# Sheet1.net
KiCad netlist of a schematic drawn in Altium Designer
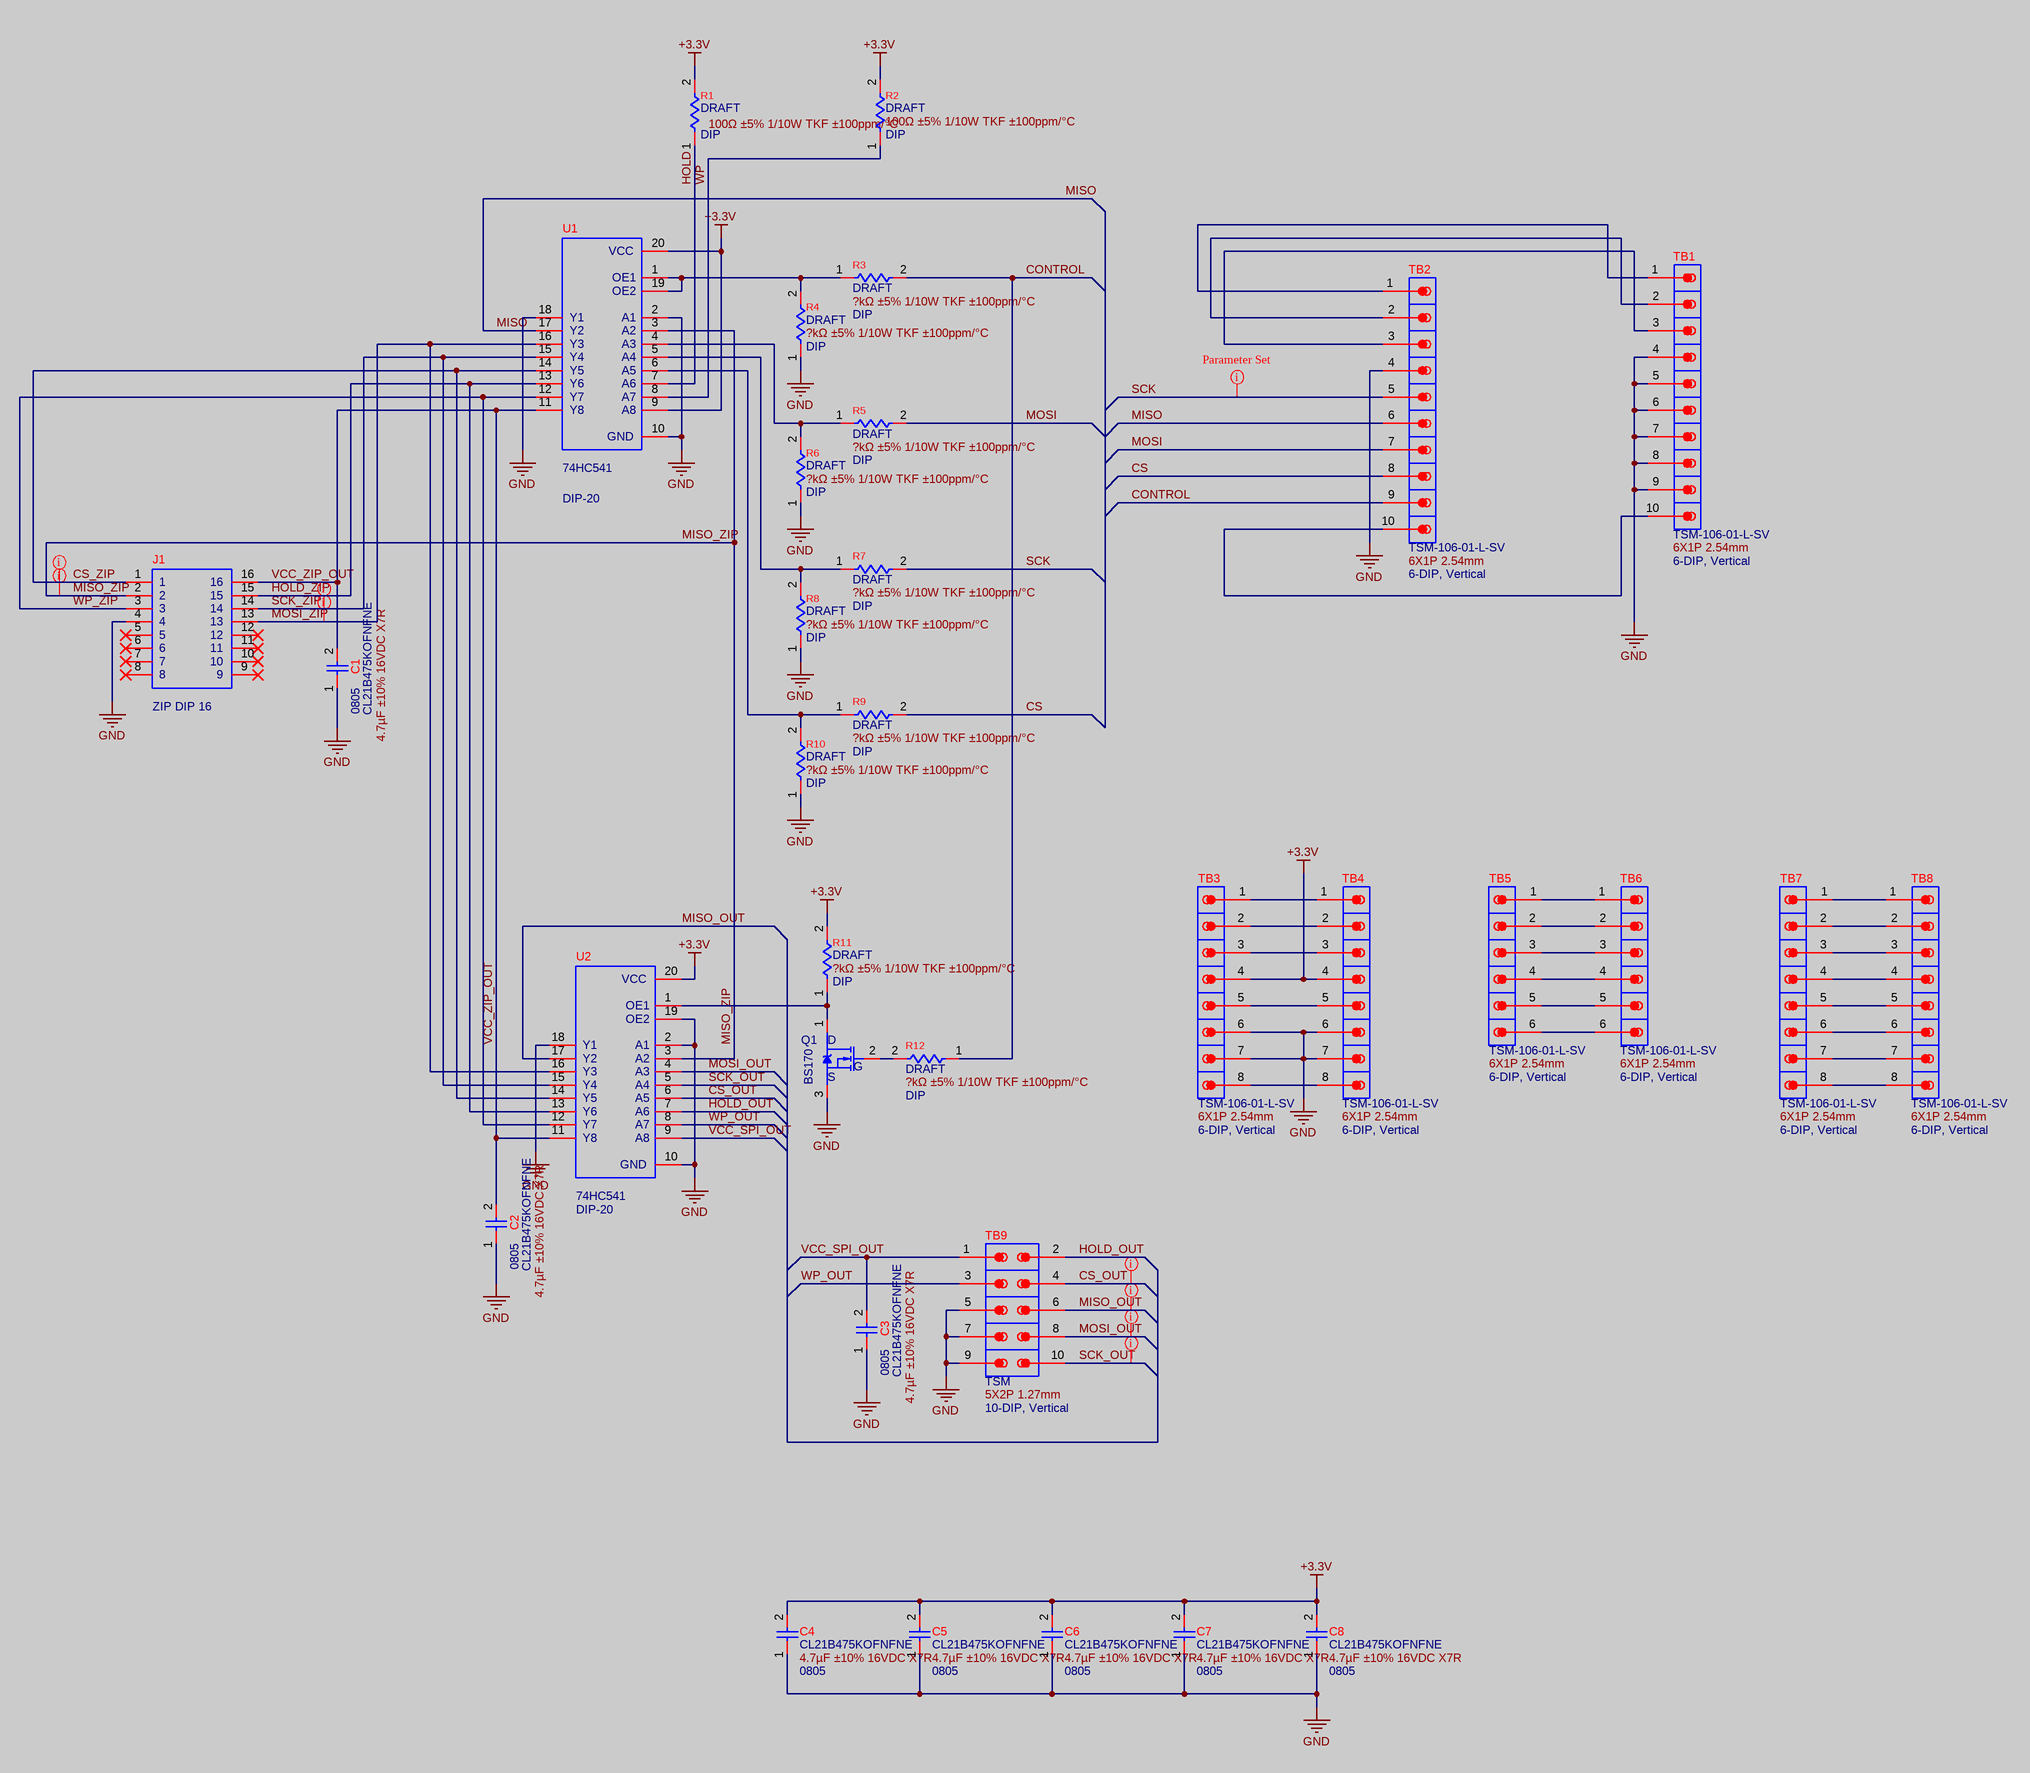
[diagram p0: Sheet1.SchDoc]

(export (version "E")
  (design (tool "Eeschema 10.0.6"))
  (components
    (comp (ref "C1")
      (value "CL21B475KOFNFNE")
      (footprint "0805_CAP_H1.4mm")
      (description "CAP CER 0805 \r\n4.7µF ±10% 25V X7R")
      (fields
        (field (name "MANUFACTURER") "SAMSUNG")
        (field (name "ALTIUM_VALUE") "4.7µF ±10% 16VDC X7R")
        (field (name "PACKAGE / CASE CODE") "0805")
      )
      (libsource (lib "Components_Library_Magenta_City") (part "CL21B475KOFNFNE"))
    )
    (comp (ref "C2")
      (value "CL21B475KOFNFNE")
      (footprint "0805_CAP_H1.4mm")
      (description "CAP CER 0805 \r\n4.7µF ±10% 25V X7R")
      (fields
        (field (name "MANUFACTURER") "SAMSUNG")
        (field (name "ALTIUM_VALUE") "4.7µF ±10% 16VDC X7R")
        (field (name "PACKAGE / CASE CODE") "0805")
      )
      (libsource (lib "Components_Library_Magenta_City") (part "CL21B475KOFNFNE"))
    )
    (comp (ref "C3")
      (value "CL21B475KOFNFNE")
      (footprint "0805_CAP_H1.4mm")
      (description "CAP CER 0805 \r\n4.7µF ±10% 25V X7R")
      (fields
        (field (name "MANUFACTURER") "SAMSUNG")
        (field (name "ALTIUM_VALUE") "4.7µF ±10% 16VDC X7R")
        (field (name "PACKAGE / CASE CODE") "0805")
      )
      (libsource (lib "Components_Library_Magenta_City") (part "CL21B475KOFNFNE"))
    )
    (comp (ref "C4")
      (value "CL21B475KOFNFNE")
      (footprint "0805_CAP_H1.4mm")
      (description "CAP CER 0805 \r\n4.7µF ±10% 25V X7R")
      (fields
        (field (name "MANUFACTURER") "SAMSUNG")
        (field (name "ALTIUM_VALUE") "4.7µF ±10% 16VDC X7R")
        (field (name "PACKAGE / CASE CODE") "0805")
      )
      (libsource (lib "Components_Library_Magenta_City") (part "CL21B475KOFNFNE"))
    )
    (comp (ref "C5")
      (value "CL21B475KOFNFNE")
      (footprint "0805_CAP_H1.4mm")
      (description "CAP CER 0805 \r\n4.7µF ±10% 25V X7R")
      (fields
        (field (name "MANUFACTURER") "SAMSUNG")
        (field (name "ALTIUM_VALUE") "4.7µF ±10% 16VDC X7R")
        (field (name "PACKAGE / CASE CODE") "0805")
      )
      (libsource (lib "Components_Library_Magenta_City") (part "CL21B475KOFNFNE"))
    )
    (comp (ref "C6")
      (value "CL21B475KOFNFNE")
      (footprint "0805_CAP_H1.4mm")
      (description "CAP CER 0805 \r\n4.7µF ±10% 25V X7R")
      (fields
        (field (name "MANUFACTURER") "SAMSUNG")
        (field (name "ALTIUM_VALUE") "4.7µF ±10% 16VDC X7R")
        (field (name "PACKAGE / CASE CODE") "0805")
      )
      (libsource (lib "Components_Library_Magenta_City") (part "CL21B475KOFNFNE"))
    )
    (comp (ref "C7")
      (value "CL21B475KOFNFNE")
      (footprint "0805_CAP_H1.4mm")
      (description "CAP CER 0805 \r\n4.7µF ±10% 25V X7R")
      (fields
        (field (name "MANUFACTURER") "SAMSUNG")
        (field (name "ALTIUM_VALUE") "4.7µF ±10% 16VDC X7R")
        (field (name "PACKAGE / CASE CODE") "0805")
      )
      (libsource (lib "Components_Library_Magenta_City") (part "CL21B475KOFNFNE"))
    )
    (comp (ref "C8")
      (value "CL21B475KOFNFNE")
      (footprint "0805_CAP_H1.4mm")
      (description "CAP CER 0805 \r\n4.7µF ±10% 25V X7R")
      (fields
        (field (name "MANUFACTURER") "SAMSUNG")
        (field (name "ALTIUM_VALUE") "4.7µF ±10% 16VDC X7R")
        (field (name "PACKAGE / CASE CODE") "0805")
      )
      (libsource (lib "Components_Library_Magenta_City") (part "CL21B475KOFNFNE"))
    )
    (comp (ref "J1")
      (value "ZIP DIP 16")
      (footprint "DIP-16")
      (description "3M™ Textool™.100” (2.54 mm) DIP Sockets\r\nZIP DIP")
      (fields (field (name "MANUFACTURER") "TI"))
      (libsource (lib "Magenta_City_lib") (part "ZIP DIP 16"))
    )
    (comp (ref "Q1")
      (value "BS170")
      (footprint "TO-226-AA")
      (description "MOSFET N-Channel")
      (libsource (lib "Components_Library_Magenta_City") (part "BS170"))
    )
    (comp (ref "R1")
      (value "DRAFT")
      (footprint "RES-DIP")
      (description "RES DRAFT DIP")
      (fields
        (field (name "ALTIUM_VALUE") "100Ω ±5% 1/10W TKF ±100ppm/°C")
        (field (name "PACKAGE / CASE CODE") "DIP")
      )
      (libsource (lib "Components_Library_Magenta_City") (part "Res DIP"))
    )
    (comp (ref "R2")
      (value "DRAFT")
      (footprint "RES-DIP")
      (description "RES DRAFT DIP")
      (fields
        (field (name "ALTIUM_VALUE") "100Ω ±5% 1/10W TKF ±100ppm/°C")
        (field (name "PACKAGE / CASE CODE") "DIP")
      )
      (libsource (lib "Components_Library_Magenta_City") (part "Res DIP"))
    )
    (comp (ref "R3")
      (value "DRAFT")
      (footprint "RES-DIP")
      (description "RES DRAFT DIP")
      (fields
        (field (name "ALTIUM_VALUE") "?kΩ ±5% 1/10W TKF ±100ppm/°C")
        (field (name "PACKAGE / CASE CODE") "DIP")
      )
      (libsource (lib "Components_Library_Magenta_City") (part "Res DIP"))
    )
    (comp (ref "R4")
      (value "DRAFT")
      (footprint "RES-DIP")
      (description "RES DRAFT DIP")
      (fields
        (field (name "ALTIUM_VALUE") "?kΩ ±5% 1/10W TKF ±100ppm/°C")
        (field (name "PACKAGE / CASE CODE") "DIP")
      )
      (libsource (lib "Components_Library_Magenta_City") (part "Res DIP"))
    )
    (comp (ref "R5")
      (value "DRAFT")
      (footprint "RES-DIP")
      (description "RES DRAFT DIP")
      (fields
        (field (name "ALTIUM_VALUE") "?kΩ ±5% 1/10W TKF ±100ppm/°C")
        (field (name "PACKAGE / CASE CODE") "DIP")
      )
      (libsource (lib "Components_Library_Magenta_City") (part "Res DIP"))
    )
    (comp (ref "R6")
      (value "DRAFT")
      (footprint "RES-DIP")
      (description "RES DRAFT DIP")
      (fields
        (field (name "ALTIUM_VALUE") "?kΩ ±5% 1/10W TKF ±100ppm/°C")
        (field (name "PACKAGE / CASE CODE") "DIP")
      )
      (libsource (lib "Components_Library_Magenta_City") (part "Res DIP"))
    )
    (comp (ref "R7")
      (value "DRAFT")
      (footprint "RES-DIP")
      (description "RES DRAFT DIP")
      (fields
        (field (name "ALTIUM_VALUE") "?kΩ ±5% 1/10W TKF ±100ppm/°C")
        (field (name "PACKAGE / CASE CODE") "DIP")
      )
      (libsource (lib "Components_Library_Magenta_City") (part "Res DIP"))
    )
    (comp (ref "R8")
      (value "DRAFT")
      (footprint "RES-DIP")
      (description "RES DRAFT DIP")
      (fields
        (field (name "ALTIUM_VALUE") "?kΩ ±5% 1/10W TKF ±100ppm/°C")
        (field (name "PACKAGE / CASE CODE") "DIP")
      )
      (libsource (lib "Components_Library_Magenta_City") (part "Res DIP"))
    )
    (comp (ref "R9")
      (value "DRAFT")
      (footprint "RES-DIP")
      (description "RES DRAFT DIP")
      (fields
        (field (name "ALTIUM_VALUE") "?kΩ ±5% 1/10W TKF ±100ppm/°C")
        (field (name "PACKAGE / CASE CODE") "DIP")
      )
      (libsource (lib "Components_Library_Magenta_City") (part "Res DIP"))
    )
    (comp (ref "R10")
      (value "DRAFT")
      (footprint "RES-DIP")
      (description "RES DRAFT DIP")
      (fields
        (field (name "ALTIUM_VALUE") "?kΩ ±5% 1/10W TKF ±100ppm/°C")
        (field (name "PACKAGE / CASE CODE") "DIP")
      )
      (libsource (lib "Components_Library_Magenta_City") (part "Res DIP"))
    )
    (comp (ref "R11")
      (value "DRAFT")
      (footprint "RES-DIP")
      (description "RES DRAFT DIP")
      (fields
        (field (name "ALTIUM_VALUE") "?kΩ ±5% 1/10W TKF ±100ppm/°C")
        (field (name "PACKAGE / CASE CODE") "DIP")
      )
      (libsource (lib "Components_Library_Magenta_City") (part "Res DIP"))
    )
    (comp (ref "R12")
      (value "DRAFT")
      (footprint "RES-DIP")
      (description "RES DRAFT DIP")
      (fields
        (field (name "ALTIUM_VALUE") "?kΩ ±5% 1/10W TKF ±100ppm/°C")
        (field (name "PACKAGE / CASE CODE") "DIP")
      )
      (libsource (lib "Components_Library_Magenta_City") (part "Res DIP"))
    )
    (comp (ref "TB1")
      (value "TSM-106-01-L-SV")
      (footprint "SW10")
      (description "TERMINAL STRIP \r\n2.54mm 6X1P \r\nSMD Vertical")
      (fields
        (field (name "MANUFACTURER") "Samtec")
        (field (name "ALTIUM_VALUE") "6X1P 2.54mm")
        (field (name "PACKAGE / CASE CODE") "6-DIP, Vertical")
      )
      (libsource (lib "Components_Library_Magenta_City") (part "SW-10"))
    )
    (comp (ref "TB2")
      (value "TSM-106-01-L-SV")
      (footprint "SW10")
      (description "TERMINAL STRIP \r\n2.54mm 6X1P \r\nSMD Vertical")
      (fields
        (field (name "MANUFACTURER") "Samtec")
        (field (name "ALTIUM_VALUE") "6X1P 2.54mm")
        (field (name "PACKAGE / CASE CODE") "6-DIP, Vertical")
      )
      (libsource (lib "Components_Library_Magenta_City") (part "SW-10"))
    )
    (comp (ref "TB3")
      (value "TSM-106-01-L-SV")
      (footprint "SW8")
      (description "TERMINAL STRIP \r\n2.54mm 6X1P \r\nSMD Vertical")
      (fields
        (field (name "MANUFACTURER") "Samtec")
        (field (name "ALTIUM_VALUE") "6X1P 2.54mm")
        (field (name "PACKAGE / CASE CODE") "6-DIP, Vertical")
      )
      (libsource (lib "") (part "SW-8_1"))
    )
    (comp (ref "TB4")
      (value "TSM-106-01-L-SV")
      (footprint "SW8")
      (description "TERMINAL STRIP \r\n2.54mm 6X1P \r\nSMD Vertical")
      (fields
        (field (name "MANUFACTURER") "Samtec")
        (field (name "ALTIUM_VALUE") "6X1P 2.54mm")
        (field (name "PACKAGE / CASE CODE") "6-DIP, Vertical")
      )
      (libsource (lib "Components_Library_Magenta_City") (part "SW-8"))
    )
    (comp (ref "TB5")
      (value "TSM-106-01-L-SV")
      (footprint "SW6")
      (description "TERMINAL STRIP \r\n2.54mm 6X1P \r\nSMD Vertical")
      (fields
        (field (name "MANUFACTURER") "Samtec")
        (field (name "ALTIUM_VALUE") "6X1P 2.54mm")
        (field (name "PACKAGE / CASE CODE") "6-DIP, Vertical")
      )
      (libsource (lib "") (part "SW-6_1"))
    )
    (comp (ref "TB6")
      (value "TSM-106-01-L-SV")
      (footprint "SW6")
      (description "TERMINAL STRIP \r\n2.54mm 6X1P \r\nSMD Vertical")
      (fields
        (field (name "MANUFACTURER") "Samtec")
        (field (name "ALTIUM_VALUE") "6X1P 2.54mm")
        (field (name "PACKAGE / CASE CODE") "6-DIP, Vertical")
      )
      (libsource (lib "Components_Library_Magenta_City") (part "SW-6"))
    )
    (comp (ref "TB7")
      (value "TSM-106-01-L-SV")
      (footprint "SW8")
      (description "TERMINAL STRIP \r\n2.54mm 6X1P \r\nSMD Vertical")
      (fields
        (field (name "MANUFACTURER") "Samtec")
        (field (name "ALTIUM_VALUE") "6X1P 2.54mm")
        (field (name "PACKAGE / CASE CODE") "6-DIP, Vertical")
      )
      (libsource (lib "") (part "SW-8_1"))
    )
    (comp (ref "TB8")
      (value "TSM-106-01-L-SV")
      (footprint "SW8")
      (description "TERMINAL STRIP \r\n2.54mm 6X1P \r\nSMD Vertical")
      (fields
        (field (name "MANUFACTURER") "Samtec")
        (field (name "ALTIUM_VALUE") "6X1P 2.54mm")
        (field (name "PACKAGE / CASE CODE") "6-DIP, Vertical")
      )
      (libsource (lib "Components_Library_Magenta_City") (part "SW-8"))
    )
    (comp (ref "TB9")
      (value "TSM")
      (footprint "SW10x2_1.27")
      (description "TERMINAL STRIP \r\n1.27mm 5X2P \r\nDIP Vertical")
      (fields
        (field (name "MANUFACTURER") "Samtec")
        (field (name "ALTIUM_VALUE") "5X2P 1.27mm")
        (field (name "PACKAGE / CASE CODE") "10-DIP, Vertical")
      )
      (libsource (lib "Components_Library_Magenta_City") (part "TSM-1"))
    )
    (comp (ref "U1")
      (value "74HC541")
      (footprint "CDIP-20")
      (description "DIP-20")
      (fields (field (name "MANUFACTURER") "TI") (field (name "PACKAGE / CASE CODE") "DIP-20"))
      (libsource (lib "Components_Library_Magenta_City") (part "74HC541"))
    )
    (comp (ref "U2")
      (value "74HC541")
      (footprint "CDIP-20")
      (description "DIP-20")
      (fields (field (name "MANUFACTURER") "TI") (field (name "PACKAGE / CASE CODE") "DIP-20"))
      (libsource (lib "Components_Library_Magenta_City") (part "74HC541"))
    )
  )
  (nets
    (net (code "1") (name "+3.3V") (class "Default")
      (node (ref "C4") (pin "2") (pinfunction "2_2") (pintype "passive"))
      (node (ref "C5") (pin "2") (pinfunction "2_2") (pintype "passive"))
      (node (ref "C6") (pin "2") (pinfunction "2_2") (pintype "passive"))
      (node (ref "C7") (pin "2") (pinfunction "2_2") (pintype "passive"))
      (node (ref "C8") (pin "2") (pinfunction "2_2") (pintype "passive"))
      (node (ref "R1") (pin "2") (pinfunction "2_2") (pintype "passive"))
      (node (ref "R11") (pin "2") (pinfunction "2_2") (pintype "passive"))
      (node (ref "R2") (pin "2") (pinfunction "2_2") (pintype "passive"))
      (node (ref "TB3") (pin "4") (pinfunction "4_4") (pintype "passive"))
      (node (ref "TB4") (pin "4") (pinfunction "4_4") (pintype "passive"))
      (node (ref "U1") (pin "20") (pinfunction "VCC_20") (pintype "power_in"))
      (node (ref "U1") (pin "9") (pinfunction "A8_9") (pintype "passive"))
      (node (ref "U2") (pin "20") (pinfunction "VCC_20") (pintype "power_in"))
    )
    (net (code "2") (name "/CONTROL") (class "Default")
      (node (ref "R12") (pin "1") (pinfunction "1_1") (pintype "passive"))
      (node (ref "R3") (pin "2") (pinfunction "2_2") (pintype "passive"))
      (node (ref "TB2") (pin "9") (pinfunction "9_9") (pintype "passive"))
    )
    (net (code "3") (name "/CS") (class "Default")
      (node (ref "R9") (pin "2") (pinfunction "2_2") (pintype "passive"))
      (node (ref "TB2") (pin "8") (pinfunction "8_8") (pintype "passive"))
    )
    (net (code "4") (name "/CS_OUT") (class "Default")
      (node (ref "TB9") (pin "4") (pinfunction "4_4") (pintype "passive"))
      (node (ref "U2") (pin "6") (pinfunction "A5_6") (pintype "passive"))
    )
    (net (code "5") (name "/CS_ZIP") (class "Default")
      (node (ref "J1") (pin "1") (pinfunction "1_1") (pintype "passive"))
      (node (ref "U1") (pin "14") (pinfunction "Y5_14") (pintype "passive"))
      (node (ref "U2") (pin "14") (pinfunction "Y5_14") (pintype "passive"))
    )
    (net (code "6") (name "/HOLD") (class "Default")
      (node (ref "R1") (pin "1") (pinfunction "1_1") (pintype "passive"))
      (node (ref "U1") (pin "7") (pinfunction "A6_7") (pintype "passive"))
    )
    (net (code "7") (name "/HOLD_OUT") (class "Default")
      (node (ref "TB9") (pin "2") (pinfunction "2_2") (pintype "passive"))
      (node (ref "U2") (pin "7") (pinfunction "A6_7") (pintype "passive"))
    )
    (net (code "8") (name "/HOLD_ZIP") (class "Default")
      (node (ref "J1") (pin "15") (pinfunction "15_15") (pintype "passive"))
      (node (ref "U1") (pin "13") (pinfunction "Y6_13") (pintype "passive"))
      (node (ref "U2") (pin "13") (pinfunction "Y6_13") (pintype "passive"))
    )
    (net (code "9") (name "/MISO") (class "Default")
      (node (ref "TB2") (pin "6") (pinfunction "6_6") (pintype "passive"))
      (node (ref "U1") (pin "17") (pinfunction "Y2_17") (pintype "passive"))
    )
    (net (code "10") (name "/MISO_OUT") (class "Default")
      (node (ref "TB9") (pin "6") (pinfunction "6_6") (pintype "passive"))
      (node (ref "U2") (pin "17") (pinfunction "Y2_17") (pintype "passive"))
    )
    (net (code "11") (name "/MISO_ZIP") (class "Default")
      (node (ref "J1") (pin "2") (pinfunction "2_2") (pintype "passive"))
      (node (ref "U1") (pin "3") (pinfunction "A2_3") (pintype "passive"))
      (node (ref "U2") (pin "3") (pinfunction "A2_3") (pintype "passive"))
    )
    (net (code "12") (name "/MOSI") (class "Default")
      (node (ref "R5") (pin "2") (pinfunction "2_2") (pintype "passive"))
      (node (ref "TB2") (pin "7") (pinfunction "7_7") (pintype "passive"))
    )
    (net (code "13") (name "/MOSI_OUT") (class "Default")
      (node (ref "TB9") (pin "8") (pinfunction "8_8") (pintype "passive"))
      (node (ref "U2") (pin "4") (pinfunction "A3_4") (pintype "passive"))
    )
    (net (code "14") (name "/MOSI_ZIP") (class "Default")
      (node (ref "J1") (pin "13") (pinfunction "13_13") (pintype "passive"))
      (node (ref "U1") (pin "16") (pinfunction "Y3_16") (pintype "passive"))
      (node (ref "U2") (pin "16") (pinfunction "Y3_16") (pintype "passive"))
    )
    (net (code "15") (name "/SCK") (class "Default")
      (node (ref "R7") (pin "2") (pinfunction "2_2") (pintype "passive"))
      (node (ref "TB2") (pin "5") (pinfunction "5_5") (pintype "passive"))
    )
    (net (code "16") (name "/SCK_OUT") (class "Default")
      (node (ref "TB9") (pin "10") (pinfunction "10_10") (pintype "passive"))
      (node (ref "U2") (pin "5") (pinfunction "A4_5") (pintype "passive"))
    )
    (net (code "17") (name "/SCK_ZIP") (class "Default")
      (node (ref "J1") (pin "14") (pinfunction "14_14") (pintype "passive"))
      (node (ref "U1") (pin "15") (pinfunction "Y4_15") (pintype "passive"))
      (node (ref "U2") (pin "15") (pinfunction "Y4_15") (pintype "passive"))
    )
    (net (code "18") (name "/VCC_SPI_OUT") (class "Default")
      (node (ref "C3") (pin "2") (pinfunction "2_2") (pintype "passive"))
      (node (ref "TB9") (pin "1") (pinfunction "1_1") (pintype "passive"))
      (node (ref "U2") (pin "9") (pinfunction "A8_9") (pintype "passive"))
    )
    (net (code "19") (name "/VCC_ZIP_OUT") (class "Default")
      (node (ref "C1") (pin "2") (pinfunction "2_2") (pintype "passive"))
      (node (ref "C2") (pin "2") (pinfunction "2_2") (pintype "passive"))
      (node (ref "J1") (pin "16") (pinfunction "16_16") (pintype "passive"))
      (node (ref "U1") (pin "11") (pinfunction "Y8_11") (pintype "passive"))
      (node (ref "U2") (pin "11") (pinfunction "Y8_11") (pintype "passive"))
    )
    (net (code "20") (name "/WP") (class "Default")
      (node (ref "R2") (pin "1") (pinfunction "1_1") (pintype "passive"))
      (node (ref "U1") (pin "8") (pinfunction "A7_8") (pintype "passive"))
    )
    (net (code "21") (name "/WP_OUT") (class "Default")
      (node (ref "TB9") (pin "3") (pinfunction "3_3") (pintype "passive"))
      (node (ref "U2") (pin "8") (pinfunction "A7_8") (pintype "passive"))
    )
    (net (code "22") (name "/WP_ZIP") (class "Default")
      (node (ref "J1") (pin "3") (pinfunction "3_3") (pintype "passive"))
      (node (ref "U1") (pin "12") (pinfunction "Y7_12") (pintype "passive"))
      (node (ref "U2") (pin "12") (pinfunction "Y7_12") (pintype "passive"))
    )
    (net (code "23") (name "GND") (class "Default")
      (node (ref "C1") (pin "1") (pinfunction "1_1") (pintype "passive"))
      (node (ref "C2") (pin "1") (pinfunction "1_1") (pintype "passive"))
      (node (ref "C3") (pin "1") (pinfunction "1_1") (pintype "passive"))
      (node (ref "C4") (pin "1") (pinfunction "1_1") (pintype "passive"))
      (node (ref "C5") (pin "1") (pinfunction "1_1") (pintype "passive"))
      (node (ref "C6") (pin "1") (pinfunction "1_1") (pintype "passive"))
      (node (ref "C7") (pin "1") (pinfunction "1_1") (pintype "passive"))
      (node (ref "C8") (pin "1") (pinfunction "1_1") (pintype "passive"))
      (node (ref "J1") (pin "4") (pinfunction "4_4") (pintype "passive"))
      (node (ref "Q1") (pin "3") (pinfunction "S_3") (pintype "passive"))
      (node (ref "R10") (pin "1") (pinfunction "1_1") (pintype "passive"))
      (node (ref "R4") (pin "1") (pinfunction "1_1") (pintype "passive"))
      (node (ref "R6") (pin "1") (pinfunction "1_1") (pintype "passive"))
      (node (ref "R8") (pin "1") (pinfunction "1_1") (pintype "passive"))
      (node (ref "TB1") (pin "4") (pinfunction "4_4") (pintype "passive"))
      (node (ref "TB1") (pin "5") (pinfunction "5_5") (pintype "passive"))
      (node (ref "TB1") (pin "6") (pinfunction "6_6") (pintype "passive"))
      (node (ref "TB1") (pin "7") (pinfunction "7_7") (pintype "passive"))
      (node (ref "TB1") (pin "8") (pinfunction "8_8") (pintype "passive"))
      (node (ref "TB1") (pin "9") (pinfunction "9_9") (pintype "passive"))
      (node (ref "TB2") (pin "4") (pinfunction "4_4") (pintype "passive"))
      (node (ref "TB3") (pin "6") (pinfunction "6_6") (pintype "passive"))
      (node (ref "TB3") (pin "7") (pinfunction "7_7") (pintype "passive"))
      (node (ref "TB4") (pin "6") (pinfunction "6_6") (pintype "passive"))
      (node (ref "TB4") (pin "7") (pinfunction "7_7") (pintype "passive"))
      (node (ref "TB9") (pin "5") (pinfunction "5_5") (pintype "passive"))
      (node (ref "TB9") (pin "7") (pinfunction "7_7") (pintype "passive"))
      (node (ref "TB9") (pin "9") (pinfunction "9_9") (pintype "passive"))
      (node (ref "U1") (pin "10") (pinfunction "GND_10") (pintype "power_in"))
      (node (ref "U1") (pin "18") (pinfunction "Y1_18") (pintype "passive"))
      (node (ref "U1") (pin "2") (pinfunction "A1_2") (pintype "passive"))
      (node (ref "U2") (pin "10") (pinfunction "GND_10") (pintype "power_in"))
      (node (ref "U2") (pin "18") (pinfunction "Y1_18") (pintype "passive"))
      (node (ref "U2") (pin "19") (pinfunction "OE2_19") (pintype "passive"))
      (node (ref "U2") (pin "2") (pinfunction "A1_2") (pintype "passive"))
    )
    (net (code "24") (name "Net-(Q1-D)") (class "Default")
      (node (ref "Q1") (pin "1") (pinfunction "D_1") (pintype "passive"))
      (node (ref "R11") (pin "1") (pinfunction "1_1") (pintype "passive"))
      (node (ref "U2") (pin "1") (pinfunction "OE1_1") (pintype "passive"))
    )
    (net (code "25") (name "Net-(Q1-G)") (class "Default")
      (node (ref "Q1") (pin "2") (pinfunction "G_2") (pintype "passive"))
      (node (ref "R12") (pin "2") (pinfunction "2_2") (pintype "passive"))
    )
    (net (code "26") (name "Net-(TB1-Pad1)") (class "Default")
      (node (ref "TB1") (pin "1") (pinfunction "1_1") (pintype "passive"))
      (node (ref "TB2") (pin "1") (pinfunction "1_1") (pintype "passive"))
    )
    (net (code "27") (name "Net-(TB1-Pad2)") (class "Default")
      (node (ref "TB1") (pin "2") (pinfunction "2_2") (pintype "passive"))
      (node (ref "TB2") (pin "2") (pinfunction "2_2") (pintype "passive"))
    )
    (net (code "28") (name "Net-(TB1-Pad3)") (class "Default")
      (node (ref "TB1") (pin "3") (pinfunction "3_3") (pintype "passive"))
      (node (ref "TB2") (pin "3") (pinfunction "3_3") (pintype "passive"))
    )
    (net (code "29") (name "Net-(TB1-Pad10)") (class "Default")
      (node (ref "TB1") (pin "10") (pinfunction "10_10") (pintype "passive"))
      (node (ref "TB2") (pin "10") (pinfunction "10_10") (pintype "passive"))
    )
    (net (code "30") (name "Net-(TB3-Pad1)") (class "Default")
      (node (ref "TB3") (pin "1") (pinfunction "1_1") (pintype "passive"))
      (node (ref "TB4") (pin "1") (pinfunction "1_1") (pintype "passive"))
    )
    (net (code "31") (name "Net-(TB3-Pad2)") (class "Default")
      (node (ref "TB3") (pin "2") (pinfunction "2_2") (pintype "passive"))
      (node (ref "TB4") (pin "2") (pinfunction "2_2") (pintype "passive"))
    )
    (net (code "32") (name "Net-(TB3-Pad3)") (class "Default")
      (node (ref "TB3") (pin "3") (pinfunction "3_3") (pintype "passive"))
      (node (ref "TB4") (pin "3") (pinfunction "3_3") (pintype "passive"))
    )
    (net (code "33") (name "Net-(TB3-Pad5)") (class "Default")
      (node (ref "TB3") (pin "5") (pinfunction "5_5") (pintype "passive"))
      (node (ref "TB4") (pin "5") (pinfunction "5_5") (pintype "passive"))
    )
    (net (code "34") (name "Net-(TB3-Pad8)") (class "Default")
      (node (ref "TB3") (pin "8") (pinfunction "8_8") (pintype "passive"))
      (node (ref "TB4") (pin "8") (pinfunction "8_8") (pintype "passive"))
    )
    (net (code "35") (name "Net-(TB5-Pad1)") (class "Default")
      (node (ref "TB5") (pin "1") (pinfunction "1_1") (pintype "passive"))
      (node (ref "TB6") (pin "1") (pinfunction "1_1") (pintype "passive"))
    )
    (net (code "36") (name "Net-(TB5-Pad2)") (class "Default")
      (node (ref "TB5") (pin "2") (pinfunction "2_2") (pintype "passive"))
      (node (ref "TB6") (pin "2") (pinfunction "2_2") (pintype "passive"))
    )
    (net (code "37") (name "Net-(TB5-Pad3)") (class "Default")
      (node (ref "TB5") (pin "3") (pinfunction "3_3") (pintype "passive"))
      (node (ref "TB6") (pin "3") (pinfunction "3_3") (pintype "passive"))
    )
    (net (code "38") (name "Net-(TB5-Pad4)") (class "Default")
      (node (ref "TB5") (pin "4") (pinfunction "4_4") (pintype "passive"))
      (node (ref "TB6") (pin "4") (pinfunction "4_4") (pintype "passive"))
    )
    (net (code "39") (name "Net-(TB5-Pad5)") (class "Default")
      (node (ref "TB5") (pin "5") (pinfunction "5_5") (pintype "passive"))
      (node (ref "TB6") (pin "5") (pinfunction "5_5") (pintype "passive"))
    )
    (net (code "40") (name "Net-(TB5-Pad6)") (class "Default")
      (node (ref "TB5") (pin "6") (pinfunction "6_6") (pintype "passive"))
      (node (ref "TB6") (pin "6") (pinfunction "6_6") (pintype "passive"))
    )
    (net (code "41") (name "Net-(TB7-Pad1)") (class "Default")
      (node (ref "TB7") (pin "1") (pinfunction "1_1") (pintype "passive"))
      (node (ref "TB8") (pin "1") (pinfunction "1_1") (pintype "passive"))
    )
    (net (code "42") (name "Net-(TB7-Pad2)") (class "Default")
      (node (ref "TB7") (pin "2") (pinfunction "2_2") (pintype "passive"))
      (node (ref "TB8") (pin "2") (pinfunction "2_2") (pintype "passive"))
    )
    (net (code "43") (name "Net-(TB7-Pad3)") (class "Default")
      (node (ref "TB7") (pin "3") (pinfunction "3_3") (pintype "passive"))
      (node (ref "TB8") (pin "3") (pinfunction "3_3") (pintype "passive"))
    )
    (net (code "44") (name "Net-(TB7-Pad4)") (class "Default")
      (node (ref "TB7") (pin "4") (pinfunction "4_4") (pintype "passive"))
      (node (ref "TB8") (pin "4") (pinfunction "4_4") (pintype "passive"))
    )
    (net (code "45") (name "Net-(TB7-Pad5)") (class "Default")
      (node (ref "TB7") (pin "5") (pinfunction "5_5") (pintype "passive"))
      (node (ref "TB8") (pin "5") (pinfunction "5_5") (pintype "passive"))
    )
    (net (code "46") (name "Net-(TB7-Pad6)") (class "Default")
      (node (ref "TB7") (pin "6") (pinfunction "6_6") (pintype "passive"))
      (node (ref "TB8") (pin "6") (pinfunction "6_6") (pintype "passive"))
    )
    (net (code "47") (name "Net-(TB7-Pad7)") (class "Default")
      (node (ref "TB7") (pin "7") (pinfunction "7_7") (pintype "passive"))
      (node (ref "TB8") (pin "7") (pinfunction "7_7") (pintype "passive"))
    )
    (net (code "48") (name "Net-(TB7-Pad8)") (class "Default")
      (node (ref "TB7") (pin "8") (pinfunction "8_8") (pintype "passive"))
      (node (ref "TB8") (pin "8") (pinfunction "8_8") (pintype "passive"))
    )
    (net (code "49") (name "Net-(U1-A3)") (class "Default")
      (node (ref "R5") (pin "1") (pinfunction "1_1") (pintype "passive"))
      (node (ref "R6") (pin "2") (pinfunction "2_2") (pintype "passive"))
      (node (ref "U1") (pin "4") (pinfunction "A3_4") (pintype "passive"))
    )
    (net (code "50") (name "Net-(U1-A4)") (class "Default")
      (node (ref "R7") (pin "1") (pinfunction "1_1") (pintype "passive"))
      (node (ref "R8") (pin "2") (pinfunction "2_2") (pintype "passive"))
      (node (ref "U1") (pin "5") (pinfunction "A4_5") (pintype "passive"))
    )
    (net (code "51") (name "Net-(U1-A5)") (class "Default")
      (node (ref "R10") (pin "2") (pinfunction "2_2") (pintype "passive"))
      (node (ref "R9") (pin "1") (pinfunction "1_1") (pintype "passive"))
      (node (ref "U1") (pin "6") (pinfunction "A5_6") (pintype "passive"))
    )
    (net (code "52") (name "Net-(U1-OE1)") (class "Default")
      (node (ref "R3") (pin "1") (pinfunction "1_1") (pintype "passive"))
      (node (ref "R4") (pin "2") (pinfunction "2_2") (pintype "passive"))
      (node (ref "U1") (pin "1") (pinfunction "OE1_1") (pintype "passive"))
      (node (ref "U1") (pin "19") (pinfunction "OE2_19") (pintype "passive"))
    )
    (net (code "53") (name "unconnected-(J1-Pad5)") (class "Default")
      (node (ref "J1") (pin "5") (pinfunction "5_5") (pintype "passive+no_connect"))
    )
    (net (code "54") (name "unconnected-(J1-Pad6)") (class "Default")
      (node (ref "J1") (pin "6") (pinfunction "6_6") (pintype "passive+no_connect"))
    )
    (net (code "55") (name "unconnected-(J1-Pad7)") (class "Default")
      (node (ref "J1") (pin "7") (pinfunction "7_7") (pintype "passive+no_connect"))
    )
    (net (code "56") (name "unconnected-(J1-Pad8)") (class "Default")
      (node (ref "J1") (pin "8") (pinfunction "8_8") (pintype "passive+no_connect"))
    )
    (net (code "57") (name "unconnected-(J1-Pad9)") (class "Default")
      (node (ref "J1") (pin "9") (pinfunction "9_9") (pintype "passive+no_connect"))
    )
    (net (code "58") (name "unconnected-(J1-Pad10)") (class "Default")
      (node (ref "J1") (pin "10") (pinfunction "10_10") (pintype "passive+no_connect"))
    )
    (net (code "59") (name "unconnected-(J1-Pad11)") (class "Default")
      (node (ref "J1") (pin "11") (pinfunction "11_11") (pintype "passive+no_connect"))
    )
    (net (code "60") (name "unconnected-(J1-Pad12)") (class "Default")
      (node (ref "J1") (pin "12") (pinfunction "12_12") (pintype "passive+no_connect"))
    )
  )
)
